# E-Piano-SM.net
KiCad netlist of a schematic drawn in EAGLE
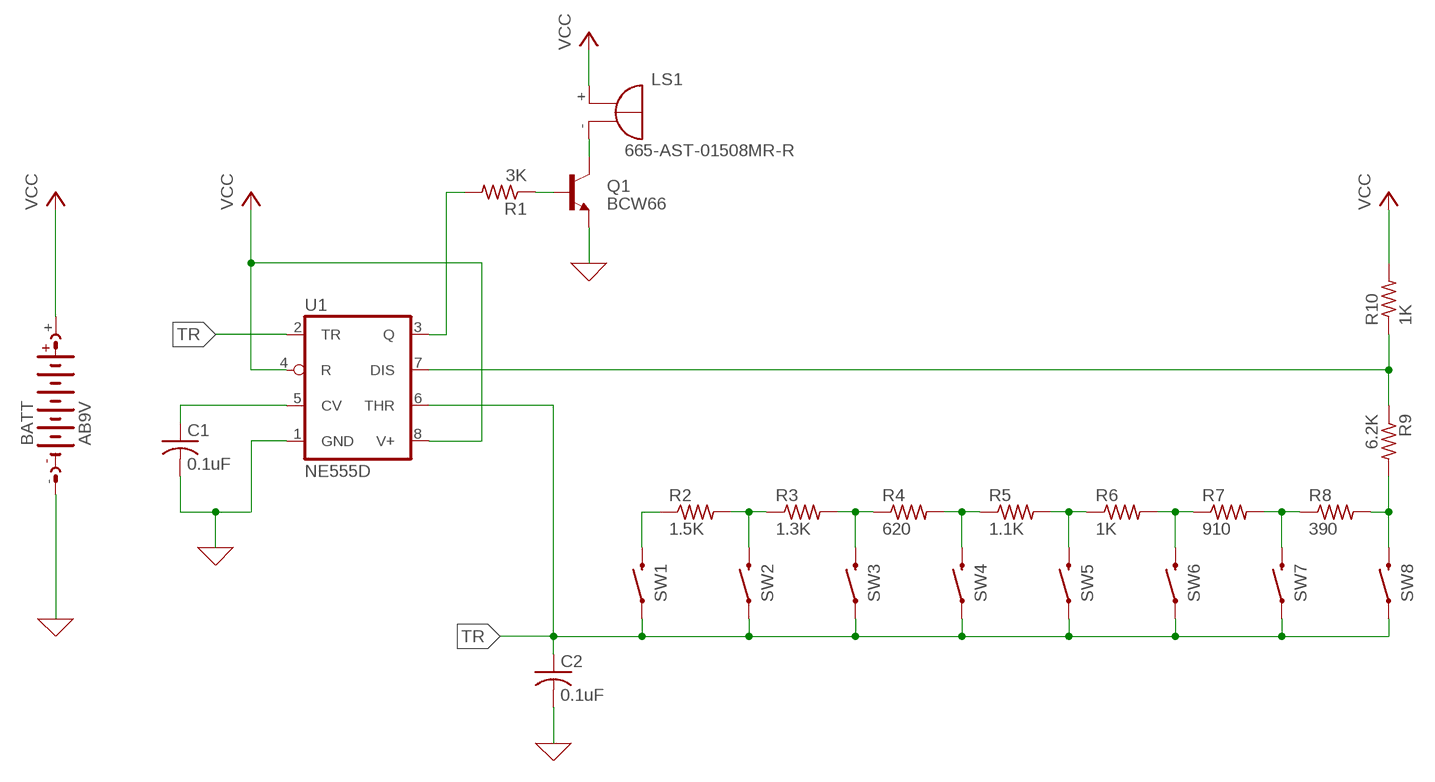
[diagram p0: schematic, sheet 1]

(export (version "E")
  (design (tool "Eeschema 10.0.6"))
  (components
    (comp (ref "BATT")
      (value "AB9V")
      (footprint "eagle-import:AB9V")
      (fields (field (name "MPN") "81-8"))
      (libsource (lib "eagle-import") (part "AB9V"))
    )
    (comp (ref "C1")
      (value "0.1uF")
      (footprint "eagle-import:C0805")
      (fields (field (name "MPN") "CC805JRX7R9BB104"))
      (libsource (lib "eagle-import") (part "C-USC0805"))
    )
    (comp (ref "C2")
      (value "0.1uF")
      (footprint "eagle-import:C0805")
      (fields (field (name "MPN") "CC805JRX7R9BB104"))
      (libsource (lib "eagle-import") (part "C-USC0805"))
    )
    (comp (ref "LS1")
      (value "F/HMB")
      (footprint "eagle-import:F_HMB")
      (fields (field (name "MOUSER#") "665-AST-01508MR-R"))
      (libsource (lib "eagle-import") (part "F/HMB"))
    )
    (comp (ref "Q1")
      (value "BCW66")
      (footprint "eagle-import:SOT23-BEC")
      (fields (field (name "MF") "FAIRCHILD SEMICONDUCTOR") (field (name "MPN") "PN2222ATF"))
      (libsource (lib "eagle-import") (part "-NPN-SOT23-BECBCW60"))
    )
    (comp (ref "R1")
      (value "3K")
      (footprint "eagle-import:R0805")
      (libsource (lib "eagle-import") (part "R-US_R0805"))
    )
    (comp (ref "R2")
      (value "1.5K")
      (footprint "eagle-import:R0805")
      (libsource (lib "eagle-import") (part "R-US_R0805"))
    )
    (comp (ref "R3")
      (value "1.3K")
      (footprint "eagle-import:R0805")
      (libsource (lib "eagle-import") (part "R-US_R0805"))
    )
    (comp (ref "R4")
      (value "620")
      (footprint "eagle-import:R0805")
      (libsource (lib "eagle-import") (part "R-US_R0805"))
    )
    (comp (ref "R5")
      (value "1.1K")
      (footprint "eagle-import:R0805")
      (libsource (lib "eagle-import") (part "R-US_R0805"))
    )
    (comp (ref "R6")
      (value "1K")
      (footprint "eagle-import:R0805")
      (libsource (lib "eagle-import") (part "R-US_R0805"))
    )
    (comp (ref "R7")
      (value "910")
      (footprint "eagle-import:R0805")
      (libsource (lib "eagle-import") (part "R-US_R0805"))
    )
    (comp (ref "R8")
      (value "390")
      (footprint "eagle-import:R0805")
      (libsource (lib "eagle-import") (part "R-US_R0805"))
    )
    (comp (ref "R9")
      (value "6.2K")
      (footprint "eagle-import:R0805")
      (libsource (lib "eagle-import") (part "R-US_R0805"))
    )
    (comp (ref "R10")
      (value "1K")
      (footprint "eagle-import:R0805")
      (libsource (lib "eagle-import") (part "R-US_R0805"))
    )
    (comp (ref "SW1")
      (value "MOMENTARY-SWITCH-SPST-SMD-6.2MM-TALL")
      (footprint "eagle-import:TACTILE_SWITCH_SMD_6.2MM_TALL")
      (fields (field (name "MPN") "1301.9317"))
      (libsource (lib "eagle-import") (part "MOMENTARY-SWITCH-SPST-SMD-6.2MM-TALL"))
    )
    (comp (ref "SW2")
      (value "MOMENTARY-SWITCH-SPST-SMD-6.2MM-TALL")
      (footprint "eagle-import:TACTILE_SWITCH_SMD_6.2MM_TALL")
      (fields (field (name "MPN") "1301.9317"))
      (libsource (lib "eagle-import") (part "MOMENTARY-SWITCH-SPST-SMD-6.2MM-TALL"))
    )
    (comp (ref "SW3")
      (value "MOMENTARY-SWITCH-SPST-SMD-6.2MM-TALL")
      (footprint "eagle-import:TACTILE_SWITCH_SMD_6.2MM_TALL")
      (fields (field (name "MPN") "1301.9317"))
      (libsource (lib "eagle-import") (part "MOMENTARY-SWITCH-SPST-SMD-6.2MM-TALL"))
    )
    (comp (ref "SW4")
      (value "MOMENTARY-SWITCH-SPST-SMD-6.2MM-TALL")
      (footprint "eagle-import:TACTILE_SWITCH_SMD_6.2MM_TALL")
      (fields (field (name "MPN") "1301.9317"))
      (libsource (lib "eagle-import") (part "MOMENTARY-SWITCH-SPST-SMD-6.2MM-TALL"))
    )
    (comp (ref "SW5")
      (value "MOMENTARY-SWITCH-SPST-SMD-6.2MM-TALL")
      (footprint "eagle-import:TACTILE_SWITCH_SMD_6.2MM_TALL")
      (fields (field (name "MPN") "1301.9317"))
      (libsource (lib "eagle-import") (part "MOMENTARY-SWITCH-SPST-SMD-6.2MM-TALL"))
    )
    (comp (ref "SW6")
      (value "MOMENTARY-SWITCH-SPST-SMD-6.2MM-TALL")
      (footprint "eagle-import:TACTILE_SWITCH_SMD_6.2MM_TALL")
      (fields (field (name "MPN") "1301.9317"))
      (libsource (lib "eagle-import") (part "MOMENTARY-SWITCH-SPST-SMD-6.2MM-TALL"))
    )
    (comp (ref "SW7")
      (value "MOMENTARY-SWITCH-SPST-SMD-6.2MM-TALL")
      (footprint "eagle-import:TACTILE_SWITCH_SMD_6.2MM_TALL")
      (fields (field (name "MPN") "1301.9317"))
      (libsource (lib "eagle-import") (part "MOMENTARY-SWITCH-SPST-SMD-6.2MM-TALL"))
    )
    (comp (ref "SW8")
      (value "MOMENTARY-SWITCH-SPST-SMD-6.2MM-TALL")
      (footprint "eagle-import:TACTILE_SWITCH_SMD_6.2MM_TALL")
      (fields (field (name "MPN") "1301.9317"))
      (libsource (lib "eagle-import") (part "MOMENTARY-SWITCH-SPST-SMD-6.2MM-TALL"))
    )
    (comp (ref "U1")
      (value "NE555D")
      (footprint "eagle-import:SO08")
      (libsource (lib "eagle-import") (part "555DNE"))
    )
  )
  (nets
    (net (code "1") (name "GND") (class "Default")
      (node (ref "BATT") (pin "-") (pinfunction "-_-") (pintype "passive"))
      (node (ref "C1") (pin "2") (pinfunction "2_2") (pintype "passive"))
      (node (ref "C2") (pin "2") (pinfunction "2_2") (pintype "passive"))
      (node (ref "Q1") (pin "E") (pinfunction "E_E") (pintype "passive"))
      (node (ref "U1") (pin "1") (pinfunction "GND_1") (pintype "power_in"))
    )
    (net (code "2") (name "Net-(LS1-Pad-)") (class "Default")
      (node (ref "LS1") (pin "-") (pinfunction "-_-") (pintype "passive"))
      (node (ref "Q1") (pin "C") (pinfunction "C_C") (pintype "passive"))
    )
    (net (code "3") (name "Net-(Q1-PadB)") (class "Default")
      (node (ref "Q1") (pin "B") (pinfunction "B_B") (pintype "passive"))
      (node (ref "R1") (pin "1") (pinfunction "1_1") (pintype "passive"))
    )
    (net (code "4") (name "Net-(SW1-2)") (class "Default")
      (node (ref "R2") (pin "1") (pinfunction "1_1") (pintype "passive"))
      (node (ref "SW1") (pin "B2") (pinfunction "2_B2") (pintype "passive"))
    )
    (net (code "5") (name "Net-(SW2-2)") (class "Default")
      (node (ref "R2") (pin "2") (pinfunction "2_2") (pintype "passive"))
      (node (ref "R3") (pin "1") (pinfunction "1_1") (pintype "passive"))
      (node (ref "SW2") (pin "B2") (pinfunction "2_B2") (pintype "passive"))
    )
    (net (code "6") (name "Net-(SW3-2)") (class "Default")
      (node (ref "R3") (pin "2") (pinfunction "2_2") (pintype "passive"))
      (node (ref "R4") (pin "1") (pinfunction "1_1") (pintype "passive"))
      (node (ref "SW3") (pin "B2") (pinfunction "2_B2") (pintype "passive"))
    )
    (net (code "7") (name "Net-(SW4-2)") (class "Default")
      (node (ref "R4") (pin "2") (pinfunction "2_2") (pintype "passive"))
      (node (ref "R5") (pin "1") (pinfunction "1_1") (pintype "passive"))
      (node (ref "SW4") (pin "B2") (pinfunction "2_B2") (pintype "passive"))
    )
    (net (code "8") (name "Net-(SW5-2)") (class "Default")
      (node (ref "R5") (pin "2") (pinfunction "2_2") (pintype "passive"))
      (node (ref "R6") (pin "1") (pinfunction "1_1") (pintype "passive"))
      (node (ref "SW5") (pin "B2") (pinfunction "2_B2") (pintype "passive"))
    )
    (net (code "9") (name "Net-(SW6-2)") (class "Default")
      (node (ref "R6") (pin "2") (pinfunction "2_2") (pintype "passive"))
      (node (ref "R7") (pin "1") (pinfunction "1_1") (pintype "passive"))
      (node (ref "SW6") (pin "B2") (pinfunction "2_B2") (pintype "passive"))
    )
    (net (code "10") (name "Net-(SW7-2)") (class "Default")
      (node (ref "R7") (pin "2") (pinfunction "2_2") (pintype "passive"))
      (node (ref "R8") (pin "1") (pinfunction "1_1") (pintype "passive"))
      (node (ref "SW7") (pin "B2") (pinfunction "2_B2") (pintype "passive"))
    )
    (net (code "11") (name "Net-(SW8-2)") (class "Default")
      (node (ref "R8") (pin "2") (pinfunction "2_2") (pintype "passive"))
      (node (ref "R9") (pin "2") (pinfunction "2_2") (pintype "passive"))
      (node (ref "SW8") (pin "B2") (pinfunction "2_B2") (pintype "passive"))
    )
    (net (code "12") (name "Net-(U1-CV)") (class "Default")
      (node (ref "C1") (pin "1") (pinfunction "1_1") (pintype "passive"))
      (node (ref "U1") (pin "5") (pinfunction "CV_5") (pintype "input"))
    )
    (net (code "13") (name "Net-(U1-DIS)") (class "Default")
      (node (ref "R10") (pin "1") (pinfunction "1_1") (pintype "passive"))
      (node (ref "R9") (pin "1") (pinfunction "1_1") (pintype "passive"))
      (node (ref "U1") (pin "7") (pinfunction "DIS_7") (pintype "input"))
    )
    (net (code "14") (name "Net-(U1-Q)") (class "Default")
      (node (ref "R1") (pin "2") (pinfunction "2_2") (pintype "passive"))
      (node (ref "U1") (pin "3") (pinfunction "Q_3") (pintype "output"))
    )
    (net (code "15") (name "TR") (class "Default")
      (node (ref "C2") (pin "1") (pinfunction "1_1") (pintype "passive"))
      (node (ref "SW1") (pin "A2") (pinfunction "1_A2") (pintype "passive"))
      (node (ref "SW2") (pin "A2") (pinfunction "1_A2") (pintype "passive"))
      (node (ref "SW3") (pin "A2") (pinfunction "1_A2") (pintype "passive"))
      (node (ref "SW4") (pin "A2") (pinfunction "1_A2") (pintype "passive"))
      (node (ref "SW5") (pin "A2") (pinfunction "1_A2") (pintype "passive"))
      (node (ref "SW6") (pin "A2") (pinfunction "1_A2") (pintype "passive"))
      (node (ref "SW7") (pin "A2") (pinfunction "1_A2") (pintype "passive"))
      (node (ref "SW8") (pin "A2") (pinfunction "1_A2") (pintype "passive"))
      (node (ref "U1") (pin "2") (pinfunction "TR_2") (pintype "input"))
      (node (ref "U1") (pin "6") (pinfunction "THR_6") (pintype "input"))
    )
    (net (code "16") (name "VCC") (class "Default")
      (node (ref "BATT") (pin "+") (pinfunction "+_+") (pintype "passive"))
      (node (ref "LS1") (pin "+") (pinfunction "+_+") (pintype "passive"))
      (node (ref "R10") (pin "2") (pinfunction "2_2") (pintype "passive"))
      (node (ref "U1") (pin "4") (pinfunction "R_4") (pintype "input"))
      (node (ref "U1") (pin "8") (pinfunction "V+_8") (pintype "power_in"))
    )
  )
)
